# Timer.net
KiCad netlist of a schematic drawn in EAGLE
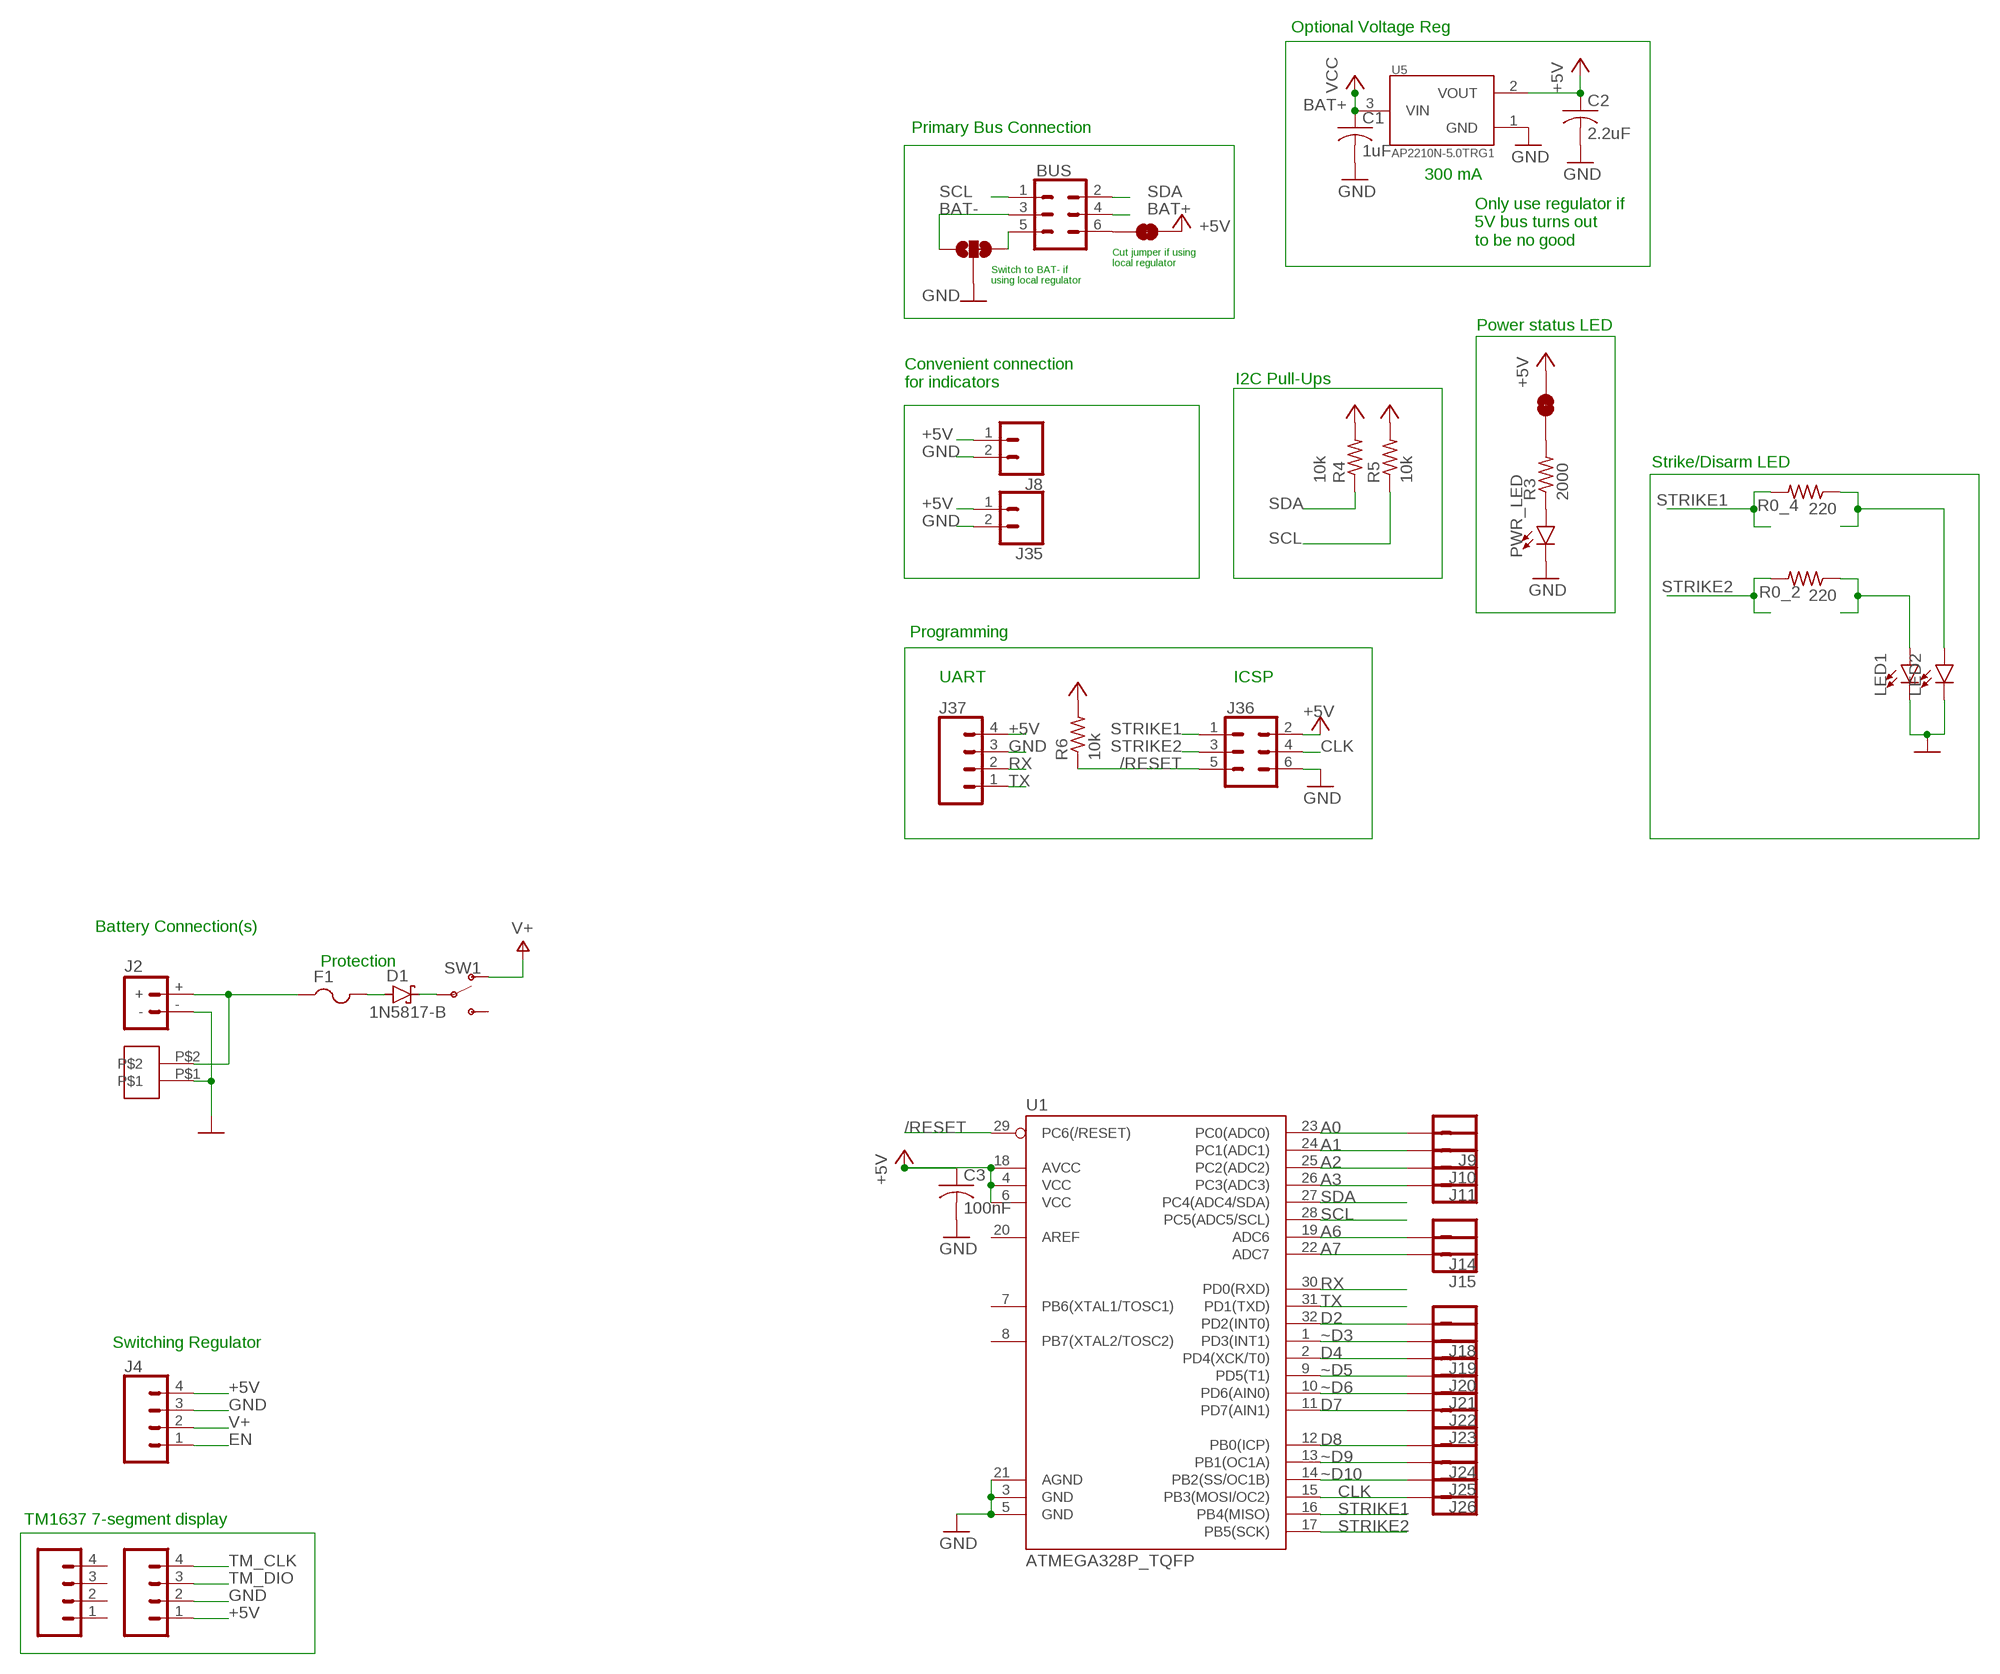
[diagram p0: schematic, sheet 1]

(export (version "E")
  (design (tool "Eeschema 10.0.6"))
  (components
    (comp (ref "BUS")
      (value "CONN_03X2SHROUD")
      (footprint "eagle-import:2X3-SHROUDED")
      (libsource (lib "eagle-import") (part "CONN_03X2SHROUD"))
    )
    (comp (ref "C1")
      (value "1uF")
      (footprint "eagle-import:C0805")
      (libsource (lib "eagle-import") (part "C-USC0805"))
    )
    (comp (ref "C2")
      (value "2.2uF")
      (footprint "eagle-import:C0805")
      (libsource (lib "eagle-import") (part "C-USC0805"))
    )
    (comp (ref "C3")
      (value "100nF")
      (footprint "eagle-import:C0805")
      (libsource (lib "eagle-import") (part "C-USC0805"))
    )
    (comp (ref "D1")
      (value "1N5817-B")
      (footprint "eagle-import:DO41-7.6")
      (libsource (lib "eagle-import") (part "1N5817-B"))
    )
    (comp (ref "F1")
      (value "FUSE")
      (footprint "eagle-import:FUSE")
      (libsource (lib "eagle-import") (part "FUSE"))
    )
    (comp (ref "J1")
      (value "CONN_01")
      (footprint "eagle-import:1X01")
      (libsource (lib "eagle-import") (part "CONN_01"))
    )
    (comp (ref "J2")
      (value "BATTERY_CONN_DEANS")
      (footprint "eagle-import:DEANS")
      (libsource (lib "eagle-import") (part "BATTERY_CONN_DEANS"))
    )
    (comp (ref "J3")
      (value "ONSHORE_OSTTG025100B")
      (footprint "eagle-import:ONSHORE_OSTTG025100B")
      (libsource (lib "eagle-import") (part "ONSHORE_OSTTG025100B"))
    )
    (comp (ref "J4")
      (value "CONN_041X04_NO_SILK")
      (footprint "eagle-import:1X04_NO_SILK")
      (libsource (lib "eagle-import") (part "CONN_041X04_NO_SILK"))
    )
    (comp (ref "J5")
      (value "CONN_041X04_NO_SILK")
      (footprint "eagle-import:1X04_NO_SILK")
      (libsource (lib "eagle-import") (part "CONN_041X04_NO_SILK"))
    )
    (comp (ref "J6")
      (value "CONN_041X04_NO_SILK")
      (footprint "eagle-import:1X04_NO_SILK")
      (libsource (lib "eagle-import") (part "CONN_041X04_NO_SILK"))
    )
    (comp (ref "J8")
      (value "CONN_02POLAR")
      (footprint "eagle-import:MOLEX-1X2")
      (libsource (lib "eagle-import") (part "CONN_02POLAR"))
    )
    (comp (ref "J9")
      (value "CONN_01")
      (footprint "eagle-import:1X01")
      (libsource (lib "eagle-import") (part "CONN_01"))
    )
    (comp (ref "J10")
      (value "CONN_01")
      (footprint "eagle-import:1X01")
      (libsource (lib "eagle-import") (part "CONN_01"))
    )
    (comp (ref "J11")
      (value "CONN_01")
      (footprint "eagle-import:1X01")
      (libsource (lib "eagle-import") (part "CONN_01"))
    )
    (comp (ref "J14")
      (value "CONN_01")
      (footprint "eagle-import:1X01")
      (libsource (lib "eagle-import") (part "CONN_01"))
    )
    (comp (ref "J15")
      (value "CONN_01")
      (footprint "eagle-import:1X01")
      (libsource (lib "eagle-import") (part "CONN_01"))
    )
    (comp (ref "J18")
      (value "CONN_01")
      (footprint "eagle-import:1X01")
      (libsource (lib "eagle-import") (part "CONN_01"))
    )
    (comp (ref "J19")
      (value "CONN_01")
      (footprint "eagle-import:1X01")
      (libsource (lib "eagle-import") (part "CONN_01"))
    )
    (comp (ref "J20")
      (value "CONN_01")
      (footprint "eagle-import:1X01")
      (libsource (lib "eagle-import") (part "CONN_01"))
    )
    (comp (ref "J21")
      (value "CONN_01")
      (footprint "eagle-import:1X01")
      (libsource (lib "eagle-import") (part "CONN_01"))
    )
    (comp (ref "J22")
      (value "CONN_01")
      (footprint "eagle-import:1X01")
      (libsource (lib "eagle-import") (part "CONN_01"))
    )
    (comp (ref "J23")
      (value "CONN_01")
      (footprint "eagle-import:1X01")
      (libsource (lib "eagle-import") (part "CONN_01"))
    )
    (comp (ref "J24")
      (value "CONN_01")
      (footprint "eagle-import:1X01")
      (libsource (lib "eagle-import") (part "CONN_01"))
    )
    (comp (ref "J25")
      (value "CONN_01")
      (footprint "eagle-import:1X01")
      (libsource (lib "eagle-import") (part "CONN_01"))
    )
    (comp (ref "J26")
      (value "CONN_01")
      (footprint "eagle-import:1X01")
      (libsource (lib "eagle-import") (part "CONN_01"))
    )
    (comp (ref "J28")
      (value "CONN_01")
      (footprint "eagle-import:1X01")
      (libsource (lib "eagle-import") (part "CONN_01"))
    )
    (comp (ref "J35")
      (value "CONN_02POLAR")
      (footprint "eagle-import:MOLEX-1X2")
      (libsource (lib "eagle-import") (part "CONN_02POLAR"))
    )
    (comp (ref "J36")
      (value "CONN_03X22X3_SILK_MALE_PTH")
      (footprint "eagle-import:2X3")
      (libsource (lib "eagle-import") (part "CONN_03X22X3_SILK_MALE_PTH"))
    )
    (comp (ref "J37")
      (value "CONN_04")
      (footprint "eagle-import:1X04")
      (libsource (lib "eagle-import") (part "CONN_04"))
    )
    (comp (ref "JP1")
      (value "JUMPER-SMT_2_NC_TRACE_SILK")
      (footprint "eagle-import:SMT-JUMPER_2_NC_TRACE_SILK")
      (libsource (lib "eagle-import") (part "JUMPER-SMT_2_NC_TRACE_SILK"))
    )
    (comp (ref "JP2")
      (value "JUMPER-SMT_3_1-NC_TRACE_SILK")
      (footprint "eagle-import:SMT-JUMPER_3_1-NC_TRACE_SILK")
      (libsource (lib "eagle-import") (part "JUMPER-SMT_3_1-NC_TRACE_SILK"))
    )
    (comp (ref "JP3")
      (value "JUMPER-SMT_2_NC_TRACE_SILK")
      (footprint "eagle-import:SMT-JUMPER_2_NC_TRACE_SILK")
      (libsource (lib "eagle-import") (part "JUMPER-SMT_2_NC_TRACE_SILK"))
    )
    (comp (ref "LED1")
      (value "LED5MM")
      (footprint "eagle-import:LED_5MM")
      (libsource (lib "eagle-import") (part "LED5MM"))
    )
    (comp (ref "LED2")
      (value "LED5MM")
      (footprint "eagle-import:LED_5MM")
      (libsource (lib "eagle-import") (part "LED5MM"))
    )
    (comp (ref "PWR_LED")
      (value "LED0603")
      (footprint "eagle-import:LED-0603")
      (libsource (lib "eagle-import") (part "LED0603"))
    )
    (comp (ref "R0_2")
      (value "220")
      (footprint "eagle-import:R0805")
      (libsource (lib "eagle-import") (part "R-US_R0805"))
    )
    (comp (ref "R0_4")
      (value "220")
      (footprint "eagle-import:R0805")
      (libsource (lib "eagle-import") (part "R-US_R0805"))
    )
    (comp (ref "R3")
      (value "2000")
      (footprint "eagle-import:R0805")
      (libsource (lib "eagle-import") (part "R-US_R0805"))
    )
    (comp (ref "R4")
      (value "10k")
      (footprint "eagle-import:R0805")
      (libsource (lib "eagle-import") (part "R-US_R0805"))
    )
    (comp (ref "R5")
      (value "10k")
      (footprint "eagle-import:R0805")
      (libsource (lib "eagle-import") (part "R-US_R0805"))
    )
    (comp (ref "R6")
      (value "10k")
      (footprint "eagle-import:0204_7")
      (libsource (lib "eagle-import") (part "R-US_0204/7"))
    )
    (comp (ref "SW1")
      (value "SLIDE_SWITCH")
      (footprint "eagle-import:SLIDE_SWITCH")
      (libsource (lib "eagle-import") (part "SLIDE_SWITCH"))
    )
    (comp (ref "U1")
      (value "ATMEGA328P_TQFP")
      (footprint "eagle-import:TQFP32-08")
      (libsource (lib "eagle-import") (part "ATMEGA328P_TQFP"))
    )
    (comp (ref "U5")
      (value "AP2210N-5.0TRG1")
      (footprint "eagle-import:SOT95P280X145-3N")
      (fields
        (field (name "DIGI-KEY_PART_NUMBER") "AP2210N-5.0TRG1DICT-ND")
        (field (name "MF") "Diodes Inc.")
      )
      (libsource (lib "eagle-import") (part "AP2210N-5.0TRG1"))
    )
  )
  (nets
    (net (code "1") (name "+5V") (class "Default")
      (node (ref "C2") (pin "1") (pinfunction "1_1") (pintype "passive"))
      (node (ref "C3") (pin "1") (pinfunction "1_1") (pintype "passive"))
      (node (ref "J35") (pin "1") (pinfunction "1_1") (pintype "passive"))
      (node (ref "J36") (pin "2") (pinfunction "2_2") (pintype "bidirectional"))
      (node (ref "J37") (pin "4") (pinfunction "4_4") (pintype "passive"))
      (node (ref "J4") (pin "4") (pinfunction "4_4") (pintype "passive"))
      (node (ref "J5") (pin "1") (pinfunction "1_1") (pintype "passive"))
      (node (ref "J8") (pin "1") (pinfunction "1_1") (pintype "passive"))
      (node (ref "JP1") (pin "2") (pinfunction "2_2") (pintype "passive"))
      (node (ref "JP3") (pin "2") (pinfunction "2_2") (pintype "passive"))
      (node (ref "R4") (pin "2") (pinfunction "2_2") (pintype "passive"))
      (node (ref "R5") (pin "2") (pinfunction "2_2") (pintype "passive"))
      (node (ref "R6") (pin "2") (pinfunction "2_2") (pintype "passive"))
      (node (ref "U1") (pin "18") (pinfunction "AVCC_18") (pintype "bidirectional"))
      (node (ref "U1") (pin "4") (pinfunction "VCC_4") (pintype "bidirectional"))
      (node (ref "U1") (pin "6") (pinfunction "VCC_6") (pintype "bidirectional"))
      (node (ref "U5") (pin "2") (pinfunction "VOUT_2") (pintype "output"))
    )
    (net (code "2") (name "/A0") (class "Default")
      (node (ref "J9") (pin "1") (pinfunction "1_1") (pintype "passive"))
      (node (ref "U1") (pin "23") (pinfunction "PC0(ADC0)_23") (pintype "bidirectional"))
    )
    (net (code "3") (name "/A1") (class "Default")
      (node (ref "J10") (pin "1") (pinfunction "1_1") (pintype "passive"))
      (node (ref "U1") (pin "24") (pinfunction "PC1(ADC1)_24") (pintype "bidirectional"))
    )
    (net (code "4") (name "/A2") (class "Default")
      (node (ref "J11") (pin "1") (pinfunction "1_1") (pintype "passive"))
      (node (ref "U1") (pin "25") (pinfunction "PC2(ADC2)_25") (pintype "bidirectional"))
    )
    (net (code "5") (name "/A3") (class "Default")
      (node (ref "J28") (pin "1") (pinfunction "1_1") (pintype "passive"))
      (node (ref "U1") (pin "26") (pinfunction "PC3(ADC3)_26") (pintype "bidirectional"))
    )
    (net (code "6") (name "/A6") (class "Default")
      (node (ref "J14") (pin "1") (pinfunction "1_1") (pintype "passive"))
      (node (ref "U1") (pin "19") (pinfunction "ADC6_19") (pintype "bidirectional"))
    )
    (net (code "7") (name "/A7") (class "Default")
      (node (ref "J15") (pin "1") (pinfunction "1_1") (pintype "passive"))
      (node (ref "U1") (pin "22") (pinfunction "ADC7_22") (pintype "bidirectional"))
    )
    (net (code "8") (name "/BAT-") (class "Default")
      (node (ref "BUS") (pin "3") (pinfunction "3_3") (pintype "bidirectional"))
      (node (ref "JP2") (pin "1") (pinfunction "1_1") (pintype "passive"))
    )
    (net (code "9") (name "/CLK") (class "Default")
      (node (ref "J1") (pin "1") (pinfunction "1_1") (pintype "passive"))
      (node (ref "J36") (pin "4") (pinfunction "4_4") (pintype "bidirectional"))
      (node (ref "U1") (pin "15") (pinfunction "PB3(MOSI/OC2)_15") (pintype "bidirectional"))
    )
    (net (code "10") (name "/D2") (class "Default")
      (node (ref "J18") (pin "1") (pinfunction "1_1") (pintype "passive"))
      (node (ref "U1") (pin "32") (pinfunction "PD2(INT0)_32") (pintype "bidirectional"))
    )
    (net (code "11") (name "/D4") (class "Default")
      (node (ref "J20") (pin "1") (pinfunction "1_1") (pintype "passive"))
      (node (ref "U1") (pin "2") (pinfunction "PD4(XCK/T0)_2") (pintype "bidirectional"))
    )
    (net (code "12") (name "/D7") (class "Default")
      (node (ref "J23") (pin "1") (pinfunction "1_1") (pintype "passive"))
      (node (ref "U1") (pin "11") (pinfunction "PD7(AIN1)_11") (pintype "bidirectional"))
    )
    (net (code "13") (name "/D8") (class "Default")
      (node (ref "J24") (pin "1") (pinfunction "1_1") (pintype "passive"))
      (node (ref "U1") (pin "12") (pinfunction "PB0(ICP)_12") (pintype "bidirectional"))
    )
    (net (code "14") (name "/EN") (class "Default")
      (node (ref "J4") (pin "1") (pinfunction "1_1") (pintype "passive"))
    )
    (net (code "15") (name "/RX") (class "Default")
      (node (ref "J37") (pin "2") (pinfunction "2_2") (pintype "passive"))
      (node (ref "U1") (pin "30") (pinfunction "PD0(RXD)_30") (pintype "bidirectional"))
    )
    (net (code "16") (name "/SCL") (class "Default")
      (node (ref "BUS") (pin "1") (pinfunction "1_1") (pintype "bidirectional"))
      (node (ref "R5") (pin "1") (pinfunction "1_1") (pintype "passive"))
      (node (ref "U1") (pin "28") (pinfunction "PC5(ADC5/SCL)_28") (pintype "bidirectional"))
    )
    (net (code "17") (name "/SDA") (class "Default")
      (node (ref "BUS") (pin "2") (pinfunction "2_2") (pintype "bidirectional"))
      (node (ref "R4") (pin "1") (pinfunction "1_1") (pintype "passive"))
      (node (ref "U1") (pin "27") (pinfunction "PC4(ADC4/SDA)_27") (pintype "bidirectional"))
    )
    (net (code "18") (name "/STRIKE1") (class "Default")
      (node (ref "J36") (pin "1") (pinfunction "1_1") (pintype "bidirectional"))
      (node (ref "R0_4") (pin "2") (pinfunction "2_2") (pintype "passive"))
      (node (ref "U1") (pin "16") (pinfunction "PB4(MISO)_16") (pintype "bidirectional"))
    )
    (net (code "19") (name "/STRIKE2") (class "Default")
      (node (ref "J36") (pin "3") (pinfunction "3_3") (pintype "bidirectional"))
      (node (ref "R0_2") (pin "2") (pinfunction "2_2") (pintype "passive"))
      (node (ref "U1") (pin "17") (pinfunction "PB5(SCK)_17") (pintype "bidirectional"))
    )
    (net (code "20") (name "/TM_CLK") (class "Default")
      (node (ref "J5") (pin "4") (pinfunction "4_4") (pintype "passive"))
    )
    (net (code "21") (name "/TM_DIO") (class "Default")
      (node (ref "J5") (pin "3") (pinfunction "3_3") (pintype "passive"))
    )
    (net (code "22") (name "/TX") (class "Default")
      (node (ref "J37") (pin "1") (pinfunction "1_1") (pintype "passive"))
      (node (ref "U1") (pin "31") (pinfunction "PD1(TXD)_31") (pintype "bidirectional"))
    )
    (net (code "23") (name "/{slash}RESET") (class "Default")
      (node (ref "J36") (pin "5") (pinfunction "5_5") (pintype "bidirectional"))
      (node (ref "R6") (pin "1") (pinfunction "1_1") (pintype "passive"))
      (node (ref "U1") (pin "29") (pinfunction "PC6(/RESET)_29") (pintype "bidirectional"))
    )
    (net (code "24") (name "/~{D3}") (class "Default")
      (node (ref "J19") (pin "1") (pinfunction "1_1") (pintype "passive"))
      (node (ref "U1") (pin "1") (pinfunction "PD3(INT1)_1") (pintype "bidirectional"))
    )
    (net (code "25") (name "/~{D5}") (class "Default")
      (node (ref "J21") (pin "1") (pinfunction "1_1") (pintype "passive"))
      (node (ref "U1") (pin "9") (pinfunction "PD5(T1)_9") (pintype "bidirectional"))
    )
    (net (code "26") (name "/~{D6}") (class "Default")
      (node (ref "J22") (pin "1") (pinfunction "1_1") (pintype "passive"))
      (node (ref "U1") (pin "10") (pinfunction "PD6(AIN0)_10") (pintype "bidirectional"))
    )
    (net (code "27") (name "/~{D9}") (class "Default")
      (node (ref "J25") (pin "1") (pinfunction "1_1") (pintype "passive"))
      (node (ref "U1") (pin "13") (pinfunction "PB1(OC1A)_13") (pintype "bidirectional"))
    )
    (net (code "28") (name "/~{D10}") (class "Default")
      (node (ref "J26") (pin "1") (pinfunction "1_1") (pintype "passive"))
      (node (ref "U1") (pin "14") (pinfunction "PB2(SS/OC1B)_14") (pintype "bidirectional"))
    )
    (net (code "29") (name "GND") (class "Default")
      (node (ref "C1") (pin "2") (pinfunction "2_2") (pintype "passive"))
      (node (ref "C2") (pin "2") (pinfunction "2_2") (pintype "passive"))
      (node (ref "C3") (pin "2") (pinfunction "2_2") (pintype "passive"))
      (node (ref "J2") (pin "-") (pinfunction "-_-") (pintype "passive"))
      (node (ref "J3") (pin "P$1") (pinfunction "P$1_P$1") (pintype "bidirectional"))
      (node (ref "J35") (pin "2") (pinfunction "2_2") (pintype "passive"))
      (node (ref "J36") (pin "6") (pinfunction "6_6") (pintype "bidirectional"))
      (node (ref "J37") (pin "3") (pinfunction "3_3") (pintype "passive"))
      (node (ref "J4") (pin "3") (pinfunction "3_3") (pintype "passive"))
      (node (ref "J5") (pin "2") (pinfunction "2_2") (pintype "passive"))
      (node (ref "J8") (pin "2") (pinfunction "2_2") (pintype "passive"))
      (node (ref "JP2") (pin "2") (pinfunction "2_2") (pintype "passive"))
      (node (ref "LED1") (pin "K") (pinfunction "C_K") (pintype "passive"))
      (node (ref "LED2") (pin "K") (pinfunction "C_K") (pintype "passive"))
      (node (ref "PWR_LED") (pin "C") (pinfunction "C_C") (pintype "passive"))
      (node (ref "U1") (pin "21") (pinfunction "AGND_21") (pintype "bidirectional"))
      (node (ref "U1") (pin "3") (pinfunction "GND_3") (pintype "bidirectional"))
      (node (ref "U1") (pin "5") (pinfunction "GND_5") (pintype "bidirectional"))
      (node (ref "U5") (pin "1") (pinfunction "GND_1") (pintype "power_in"))
    )
    (net (code "30") (name "Net-(BUS-Pad5)") (class "Default")
      (node (ref "BUS") (pin "5") (pinfunction "5_5") (pintype "bidirectional"))
      (node (ref "JP2") (pin "3") (pinfunction "3_3") (pintype "passive"))
    )
    (net (code "31") (name "Net-(BUS-Pad6)") (class "Default")
      (node (ref "BUS") (pin "6") (pinfunction "6_6") (pintype "bidirectional"))
      (node (ref "JP1") (pin "1") (pinfunction "1_1") (pintype "passive"))
    )
    (net (code "32") (name "Net-(D1-PadA)") (class "Default")
      (node (ref "D1") (pin "A") (pinfunction "A_A") (pintype "passive"))
      (node (ref "F1") (pin "P$3") (pinfunction "2_P$3") (pintype "passive"))
      (node (ref "F1") (pin "P$4") (pinfunction "2_P$4") (pintype "passive"))
    )
    (net (code "33") (name "Net-(F1-1-PadP$1)") (class "Default")
      (node (ref "F1") (pin "P$1") (pinfunction "1_P$1") (pintype "passive"))
      (node (ref "F1") (pin "P$2") (pinfunction "1_P$2") (pintype "passive"))
      (node (ref "J2") (pin "+") (pinfunction "+_+") (pintype "passive"))
      (node (ref "J3") (pin "P$2") (pinfunction "P$2_P$2") (pintype "bidirectional"))
    )
    (net (code "34") (name "Net-(JP3-Pad1)") (class "Default")
      (node (ref "JP3") (pin "1") (pinfunction "1_1") (pintype "passive"))
      (node (ref "R3") (pin "2") (pinfunction "2_2") (pintype "passive"))
    )
    (net (code "35") (name "Net-(LED1-PadA)") (class "Default")
      (node (ref "LED1") (pin "A") (pinfunction "A_A") (pintype "passive"))
      (node (ref "R0_2") (pin "1") (pinfunction "1_1") (pintype "passive"))
    )
    (net (code "36") (name "Net-(LED2-PadA)") (class "Default")
      (node (ref "LED2") (pin "A") (pinfunction "A_A") (pintype "passive"))
      (node (ref "R0_4") (pin "1") (pinfunction "1_1") (pintype "passive"))
    )
    (net (code "37") (name "Net-(PWR_LED-PadA)") (class "Default")
      (node (ref "PWR_LED") (pin "A") (pinfunction "A_A") (pintype "passive"))
      (node (ref "R3") (pin "1") (pinfunction "1_1") (pintype "passive"))
    )
    (net (code "38") (name "Net-(SW1-P)") (class "Default")
      (node (ref "D1") (pin "C") (pinfunction "C_C") (pintype "passive"))
      (node (ref "SW1") (pin "P$2") (pinfunction "P_P$2") (pintype "passive"))
    )
    (net (code "39") (name "V+") (class "Default")
      (node (ref "J4") (pin "2") (pinfunction "2_2") (pintype "passive"))
      (node (ref "SW1") (pin "P$1") (pinfunction "O_P$1") (pintype "passive"))
    )
    (net (code "40") (name "VCC") (class "Default")
      (node (ref "BUS") (pin "4") (pinfunction "4_4") (pintype "bidirectional"))
      (node (ref "C1") (pin "1") (pinfunction "1_1") (pintype "passive"))
      (node (ref "U5") (pin "3") (pinfunction "VIN_3") (pintype "input"))
    )
    (net (code "41") (name "unconnected-(J6-Pad1)") (class "Default")
      (node (ref "J6") (pin "1") (pinfunction "1_1") (pintype "passive"))
    )
    (net (code "42") (name "unconnected-(J6-Pad2)") (class "Default")
      (node (ref "J6") (pin "2") (pinfunction "2_2") (pintype "passive"))
    )
    (net (code "43") (name "unconnected-(J6-Pad3)") (class "Default")
      (node (ref "J6") (pin "3") (pinfunction "3_3") (pintype "passive"))
    )
    (net (code "44") (name "unconnected-(J6-Pad4)") (class "Default")
      (node (ref "J6") (pin "4") (pinfunction "4_4") (pintype "passive"))
    )
    (net (code "45") (name "unconnected-(SW1-S-PadP$3)") (class "Default")
      (node (ref "SW1") (pin "P$3") (pinfunction "S_P$3") (pintype "passive"))
    )
    (net (code "46") (name "unconnected-(U1-AREF-Pad20)") (class "Default")
      (node (ref "U1") (pin "20") (pinfunction "AREF_20") (pintype "bidirectional"))
    )
    (net (code "47") (name "unconnected-(U1-PB6(XTAL1{slash}TOSC1)-Pad7)") (class "Default")
      (node (ref "U1") (pin "7") (pinfunction "PB6(XTAL1/TOSC1)_7") (pintype "bidirectional"))
    )
    (net (code "48") (name "unconnected-(U1-PB7(XTAL2{slash}TOSC2)-Pad8)") (class "Default")
      (node (ref "U1") (pin "8") (pinfunction "PB7(XTAL2/TOSC2)_8") (pintype "bidirectional"))
    )
  )
)
